# InterfaceBoard.net
KiCad netlist of a schematic drawn in EAGLE
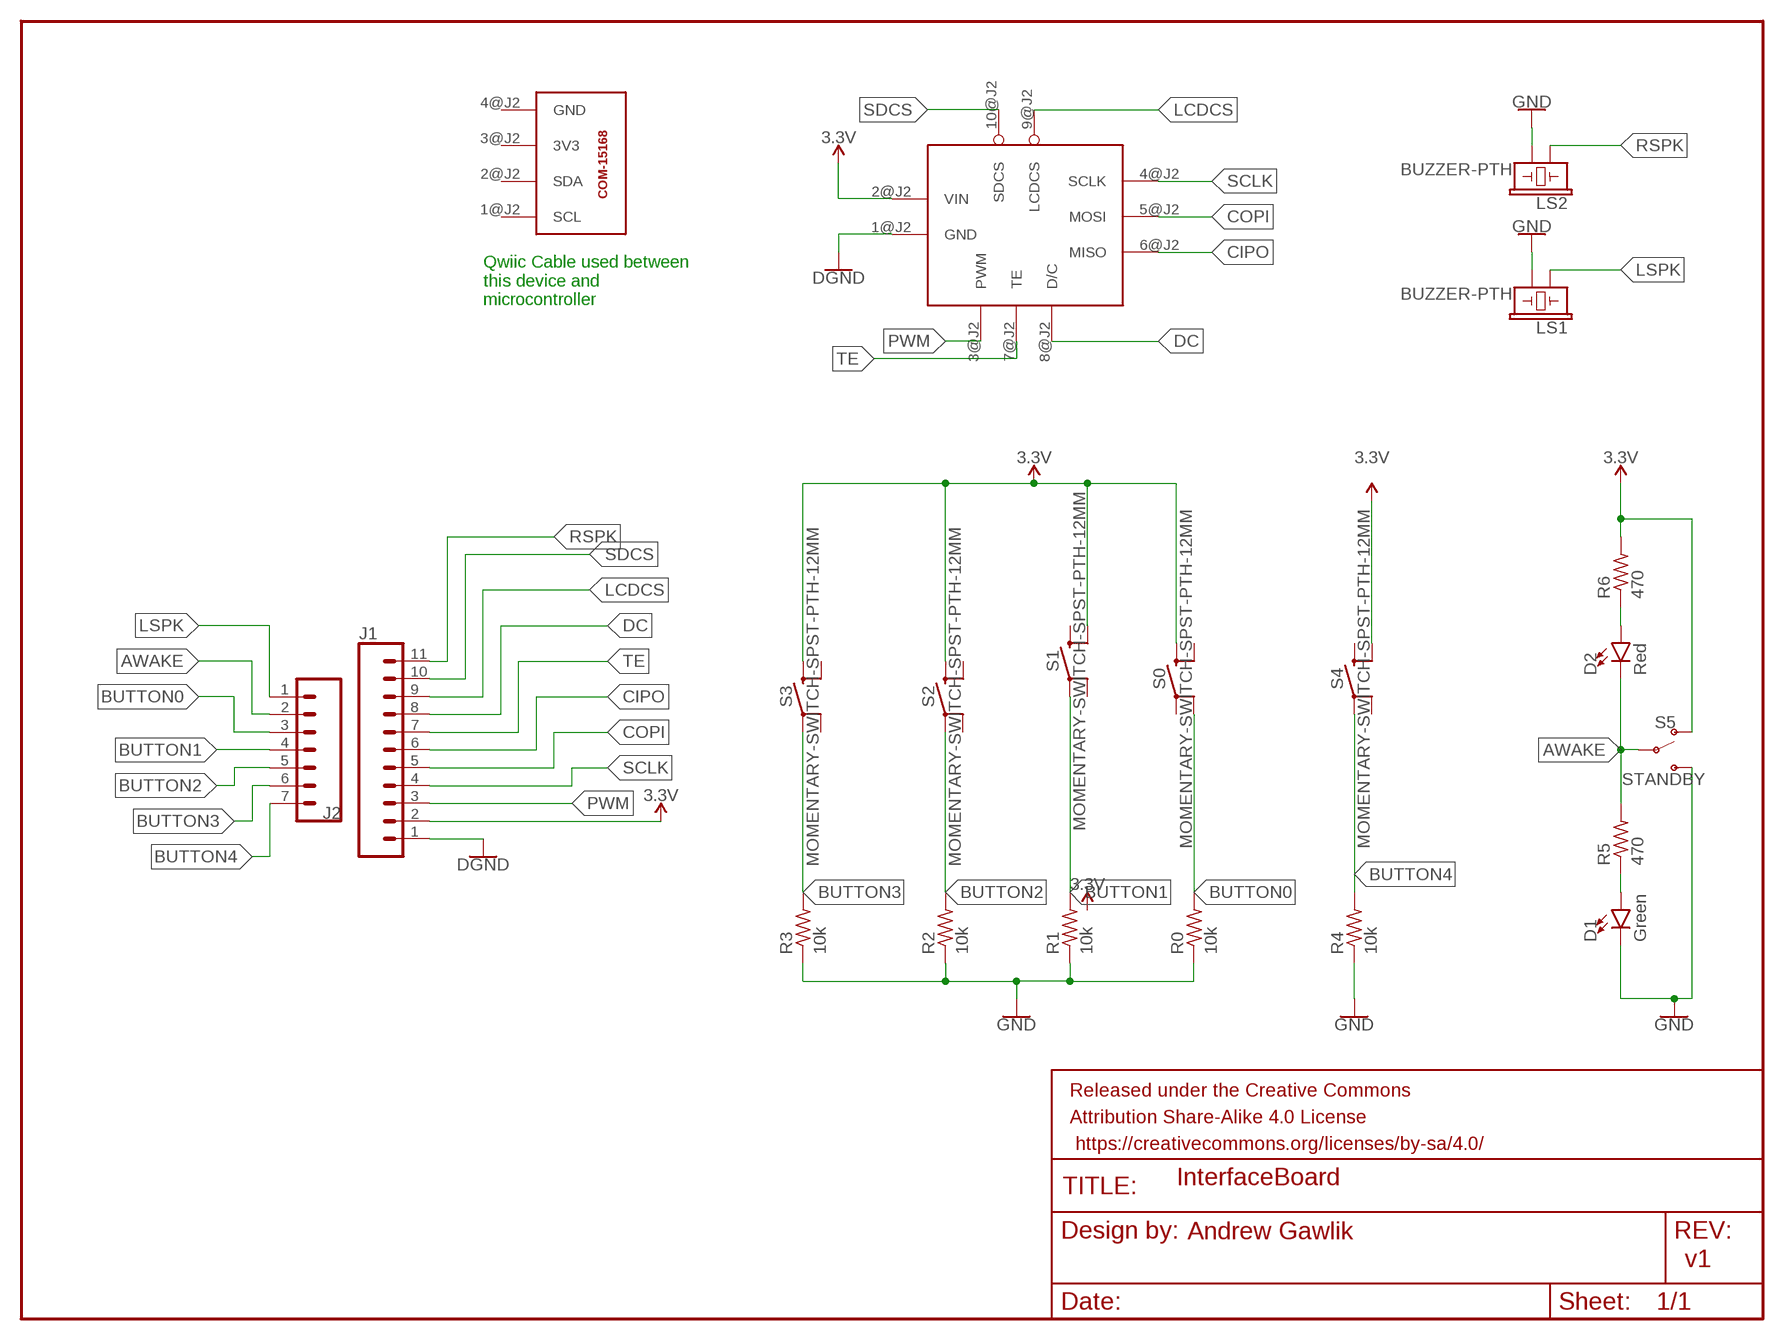
[diagram p0: schematic, sheet 1]

(export (version "E")
  (design (tool "Eeschema 10.0.6"))
  (components
    (comp (ref "A2")
      (value "TFT")
      (footprint "eagle-import:LCD-15143")
      (libsource (lib "eagle-import") (part "LCD-15143"))
    )
    (comp (ref "A3")
      (value "COM-15168")
      (footprint "eagle-import:COM-15168")
      (libsource (lib "eagle-import") (part "COM-15168"))
    )
    (comp (ref "D1")
      (value "Green")
      (footprint "eagle-import:LED_5MM-KIT")
      (libsource (lib "eagle-import") (part "LED5MM-KIT"))
    )
    (comp (ref "D2")
      (value "Red")
      (footprint "eagle-import:LED_5MM-KIT")
      (libsource (lib "eagle-import") (part "LED5MM-KIT"))
    )
    (comp (ref "FRAME1")
      (value "FRAME-LETTER")
      (footprint "eagle-import:CREATIVE_COMMONS")
      (libsource (lib "eagle-import") (part "FRAME-LETTER"))
    )
    (comp (ref "J1")
      (value "CONN_11LOCK")
      (footprint "eagle-import:1X11_LOCK")
      (libsource (lib "eagle-import") (part "CONN_11LOCK"))
    )
    (comp (ref "J2")
      (value "CONN_07LOCK")
      (footprint "eagle-import:1X07_LOCK")
      (libsource (lib "eagle-import") (part "CONN_07LOCK"))
    )
    (comp (ref "LS1")
      (value "BUZZER-PTH")
      (footprint "eagle-import:BUZZER-12MM")
      (libsource (lib "eagle-import") (part "BUZZER-PTH"))
    )
    (comp (ref "LS2")
      (value "BUZZER-PTH")
      (footprint "eagle-import:BUZZER-12MM")
      (libsource (lib "eagle-import") (part "BUZZER-PTH"))
    )
    (comp (ref "R0")
      (value "10k")
      (footprint "eagle-import:0204_5")
      (libsource (lib "eagle-import") (part "R-US_0204/5"))
    )
    (comp (ref "R1")
      (value "10k")
      (footprint "eagle-import:0204_5")
      (libsource (lib "eagle-import") (part "R-US_0204/5"))
    )
    (comp (ref "R2")
      (value "10k")
      (footprint "eagle-import:0204_5")
      (libsource (lib "eagle-import") (part "R-US_0204/5"))
    )
    (comp (ref "R3")
      (value "10k")
      (footprint "eagle-import:0204_5")
      (libsource (lib "eagle-import") (part "R-US_0204/5"))
    )
    (comp (ref "R4")
      (value "10k")
      (footprint "eagle-import:0204_5")
      (libsource (lib "eagle-import") (part "R-US_0204/5"))
    )
    (comp (ref "R5")
      (value "470")
      (footprint "eagle-import:0204_5")
      (libsource (lib "eagle-import") (part "R-US_0204/5"))
    )
    (comp (ref "R6")
      (value "470")
      (footprint "eagle-import:0204_5")
      (libsource (lib "eagle-import") (part "R-US_0204/5"))
    )
    (comp (ref "S0")
      (value "MOMENTARY-SWITCH-SPST-PTH-12MM")
      (footprint "eagle-import:TACTILE_SWITCH_PTH_12MM")
      (libsource (lib "eagle-import") (part "MOMENTARY-SWITCH-SPST-PTH-12MM"))
    )
    (comp (ref "S1")
      (value "MOMENTARY-SWITCH-SPST-PTH-12MM")
      (footprint "eagle-import:TACTILE_SWITCH_PTH_12MM")
      (libsource (lib "eagle-import") (part "MOMENTARY-SWITCH-SPST-PTH-12MM"))
    )
    (comp (ref "S2")
      (value "MOMENTARY-SWITCH-SPST-PTH-12MM")
      (footprint "eagle-import:TACTILE_SWITCH_PTH_12MM")
      (libsource (lib "eagle-import") (part "MOMENTARY-SWITCH-SPST-PTH-12MM"))
    )
    (comp (ref "S3")
      (value "MOMENTARY-SWITCH-SPST-PTH-12MM")
      (footprint "eagle-import:TACTILE_SWITCH_PTH_12MM")
      (libsource (lib "eagle-import") (part "MOMENTARY-SWITCH-SPST-PTH-12MM"))
    )
    (comp (ref "S4")
      (value "MOMENTARY-SWITCH-SPST-PTH-12MM")
      (footprint "eagle-import:TACTILE_SWITCH_PTH_12MM")
      (libsource (lib "eagle-import") (part "MOMENTARY-SWITCH-SPST-PTH-12MM"))
    )
    (comp (ref "S5")
      (value "STANDBY")
      (footprint "eagle-import:SWITCH_SPDT_PTH_11.6X4.0MM")
      (libsource (lib "eagle-import") (part "SWITCH-SPDT-PTH-11.6X4.0MM"))
    )
  )
  (nets
    (net (code "1") (name "3.3V") (class "Default")
      (node (ref "A2") (pin "2@J2") (pinfunction "VIN_2@J2") (pintype "power_in"))
      (node (ref "J1") (pin "2") (pinfunction "2_2") (pintype "passive"))
      (node (ref "R6") (pin "2") (pinfunction "2_2") (pintype "passive"))
      (node (ref "S0") (pin "3") (pinfunction "3_3") (pintype "passive"))
      (node (ref "S1") (pin "4") (pinfunction "4_4") (pintype "passive"))
      (node (ref "S2") (pin "3") (pinfunction "3_3") (pintype "passive"))
      (node (ref "S3") (pin "3") (pinfunction "3_3") (pintype "passive"))
      (node (ref "S4") (pin "4") (pinfunction "4_4") (pintype "passive"))
      (node (ref "S5") (pin "1") (pinfunction "O_1") (pintype "passive"))
    )
    (net (code "2") (name "AWAKE") (class "Default")
      (node (ref "D2") (pin "K") (pinfunction "C_K") (pintype "passive"))
      (node (ref "J2") (pin "2") (pinfunction "2_2") (pintype "passive"))
      (node (ref "R5") (pin "2") (pinfunction "2_2") (pintype "passive"))
      (node (ref "S5") (pin "2") (pinfunction "P_2") (pintype "passive"))
    )
    (net (code "3") (name "BUTTON0") (class "Default")
      (node (ref "J2") (pin "3") (pinfunction "3_3") (pintype "passive"))
      (node (ref "R0") (pin "2") (pinfunction "2_2") (pintype "passive"))
      (node (ref "S0") (pin "2") (pinfunction "2_2") (pintype "passive"))
    )
    (net (code "4") (name "BUTTON1") (class "Default")
      (node (ref "J2") (pin "4") (pinfunction "4_4") (pintype "passive"))
      (node (ref "R1") (pin "2") (pinfunction "2_2") (pintype "passive"))
      (node (ref "S1") (pin "1") (pinfunction "1_1") (pintype "passive"))
    )
    (net (code "5") (name "BUTTON2") (class "Default")
      (node (ref "J2") (pin "5") (pinfunction "5_5") (pintype "passive"))
      (node (ref "R2") (pin "2") (pinfunction "2_2") (pintype "passive"))
      (node (ref "S2") (pin "1") (pinfunction "1_1") (pintype "passive"))
    )
    (net (code "6") (name "BUTTON3") (class "Default")
      (node (ref "J2") (pin "6") (pinfunction "6_6") (pintype "passive"))
      (node (ref "R3") (pin "2") (pinfunction "2_2") (pintype "passive"))
      (node (ref "S3") (pin "1") (pinfunction "1_1") (pintype "passive"))
    )
    (net (code "7") (name "BUTTON4") (class "Default")
      (node (ref "J2") (pin "7") (pinfunction "7_7") (pintype "passive"))
      (node (ref "R4") (pin "2") (pinfunction "2_2") (pintype "passive"))
      (node (ref "S4") (pin "1") (pinfunction "1_1") (pintype "passive"))
    )
    (net (code "8") (name "CIPO") (class "Default")
      (node (ref "A2") (pin "6@J2") (pinfunction "MISO_6@J2") (pintype "output"))
      (node (ref "J1") (pin "6") (pinfunction "6_6") (pintype "passive"))
    )
    (net (code "9") (name "COPI") (class "Default")
      (node (ref "A2") (pin "5@J2") (pinfunction "MOSI_5@J2") (pintype "input"))
      (node (ref "J1") (pin "5") (pinfunction "5_5") (pintype "passive"))
    )
    (net (code "10") (name "DC") (class "Default")
      (node (ref "A2") (pin "8@J2") (pinfunction "D/C_8@J2") (pintype "bidirectional"))
      (node (ref "J1") (pin "8") (pinfunction "8_8") (pintype "passive"))
    )
    (net (code "11") (name "DGND") (class "Default")
      (node (ref "A2") (pin "1@J2") (pinfunction "GND_1@J2") (pintype "power_in"))
      (node (ref "D1") (pin "K") (pinfunction "C_K") (pintype "passive"))
      (node (ref "J1") (pin "1") (pinfunction "1_1") (pintype "passive"))
      (node (ref "LS1") (pin "-") (pinfunction "2_-") (pintype "passive"))
      (node (ref "LS2") (pin "-") (pinfunction "2_-") (pintype "passive"))
      (node (ref "R0") (pin "1") (pinfunction "1_1") (pintype "passive"))
      (node (ref "R1") (pin "1") (pinfunction "1_1") (pintype "passive"))
      (node (ref "R2") (pin "1") (pinfunction "1_1") (pintype "passive"))
      (node (ref "R3") (pin "1") (pinfunction "1_1") (pintype "passive"))
      (node (ref "R4") (pin "1") (pinfunction "1_1") (pintype "passive"))
      (node (ref "S5") (pin "3") (pinfunction "S_3") (pintype "passive"))
    )
    (net (code "12") (name "LCDCS") (class "Default")
      (node (ref "A2") (pin "9@J2") (pinfunction "LCDCS_9@J2") (pintype "input"))
      (node (ref "J1") (pin "9") (pinfunction "9_9") (pintype "passive"))
    )
    (net (code "13") (name "LSPK") (class "Default")
      (node (ref "J2") (pin "1") (pinfunction "1_1") (pintype "passive"))
      (node (ref "LS1") (pin "+") (pinfunction "1_+") (pintype "passive"))
    )
    (net (code "14") (name "Net-(D1-PadA)") (class "Default")
      (node (ref "D1") (pin "A") (pinfunction "A_A") (pintype "passive"))
      (node (ref "R5") (pin "1") (pinfunction "1_1") (pintype "passive"))
    )
    (net (code "15") (name "Net-(D2-PadA)") (class "Default")
      (node (ref "D2") (pin "A") (pinfunction "A_A") (pintype "passive"))
      (node (ref "R6") (pin "1") (pinfunction "1_1") (pintype "passive"))
    )
    (net (code "16") (name "PWM") (class "Default")
      (node (ref "A2") (pin "3@J2") (pinfunction "PWM_3@J2") (pintype "input"))
      (node (ref "J1") (pin "3") (pinfunction "3_3") (pintype "passive"))
    )
    (net (code "17") (name "RSPK") (class "Default")
      (node (ref "J1") (pin "11") (pinfunction "11_11") (pintype "passive"))
      (node (ref "LS2") (pin "+") (pinfunction "1_+") (pintype "passive"))
    )
    (net (code "18") (name "SCLK") (class "Default")
      (node (ref "A2") (pin "4@J2") (pinfunction "SCLK_4@J2") (pintype "input"))
      (node (ref "J1") (pin "4") (pinfunction "4_4") (pintype "passive"))
    )
    (net (code "19") (name "SDCS") (class "Default")
      (node (ref "A2") (pin "10@J2") (pinfunction "SDCS_10@J2") (pintype "input"))
      (node (ref "J1") (pin "10") (pinfunction "10_10") (pintype "passive"))
    )
    (net (code "20") (name "TE") (class "Default")
      (node (ref "A2") (pin "7@J2") (pinfunction "TE_7@J2") (pintype "output"))
      (node (ref "J1") (pin "7") (pinfunction "7_7") (pintype "passive"))
    )
    (net (code "21") (name "unconnected-(A3-3V3-Pad3@J2)") (class "Default")
      (node (ref "A3") (pin "3@J2") (pinfunction "3V3_3@J2") (pintype "no_connect"))
    )
    (net (code "22") (name "unconnected-(A3-GND-Pad4@J2)") (class "Default")
      (node (ref "A3") (pin "4@J2") (pinfunction "GND_4@J2") (pintype "no_connect"))
    )
    (net (code "23") (name "unconnected-(A3-SCL-Pad1@J2)") (class "Default")
      (node (ref "A3") (pin "1@J2") (pinfunction "SCL_1@J2") (pintype "no_connect"))
    )
    (net (code "24") (name "unconnected-(A3-SDA-Pad2@J2)") (class "Default")
      (node (ref "A3") (pin "2@J2") (pinfunction "SDA_2@J2") (pintype "no_connect"))
    )
    (net (code "25") (name "unconnected-(S0-Pad1)") (class "Default")
      (node (ref "S0") (pin "1") (pinfunction "1_1") (pintype "passive"))
    )
    (net (code "26") (name "unconnected-(S0-Pad4)") (class "Default")
      (node (ref "S0") (pin "4") (pinfunction "4_4") (pintype "passive"))
    )
    (net (code "27") (name "unconnected-(S1-Pad2)") (class "Default")
      (node (ref "S1") (pin "2") (pinfunction "2_2") (pintype "passive"))
    )
    (net (code "28") (name "unconnected-(S1-Pad3)") (class "Default")
      (node (ref "S1") (pin "3") (pinfunction "3_3") (pintype "passive"))
    )
    (net (code "29") (name "unconnected-(S2-Pad2)") (class "Default")
      (node (ref "S2") (pin "2") (pinfunction "2_2") (pintype "passive"))
    )
    (net (code "30") (name "unconnected-(S2-Pad4)") (class "Default")
      (node (ref "S2") (pin "4") (pinfunction "4_4") (pintype "passive"))
    )
    (net (code "31") (name "unconnected-(S3-Pad2)") (class "Default")
      (node (ref "S3") (pin "2") (pinfunction "2_2") (pintype "passive"))
    )
    (net (code "32") (name "unconnected-(S3-Pad4)") (class "Default")
      (node (ref "S3") (pin "4") (pinfunction "4_4") (pintype "passive"))
    )
    (net (code "33") (name "unconnected-(S4-Pad2)") (class "Default")
      (node (ref "S4") (pin "2") (pinfunction "2_2") (pintype "passive"))
    )
    (net (code "34") (name "unconnected-(S4-Pad3)") (class "Default")
      (node (ref "S4") (pin "3") (pinfunction "3_3") (pintype "passive"))
    )
  )
)
